# diskohedron4w_revc_autoroute.net
KiCad netlist of a schematic drawn in EAGLE
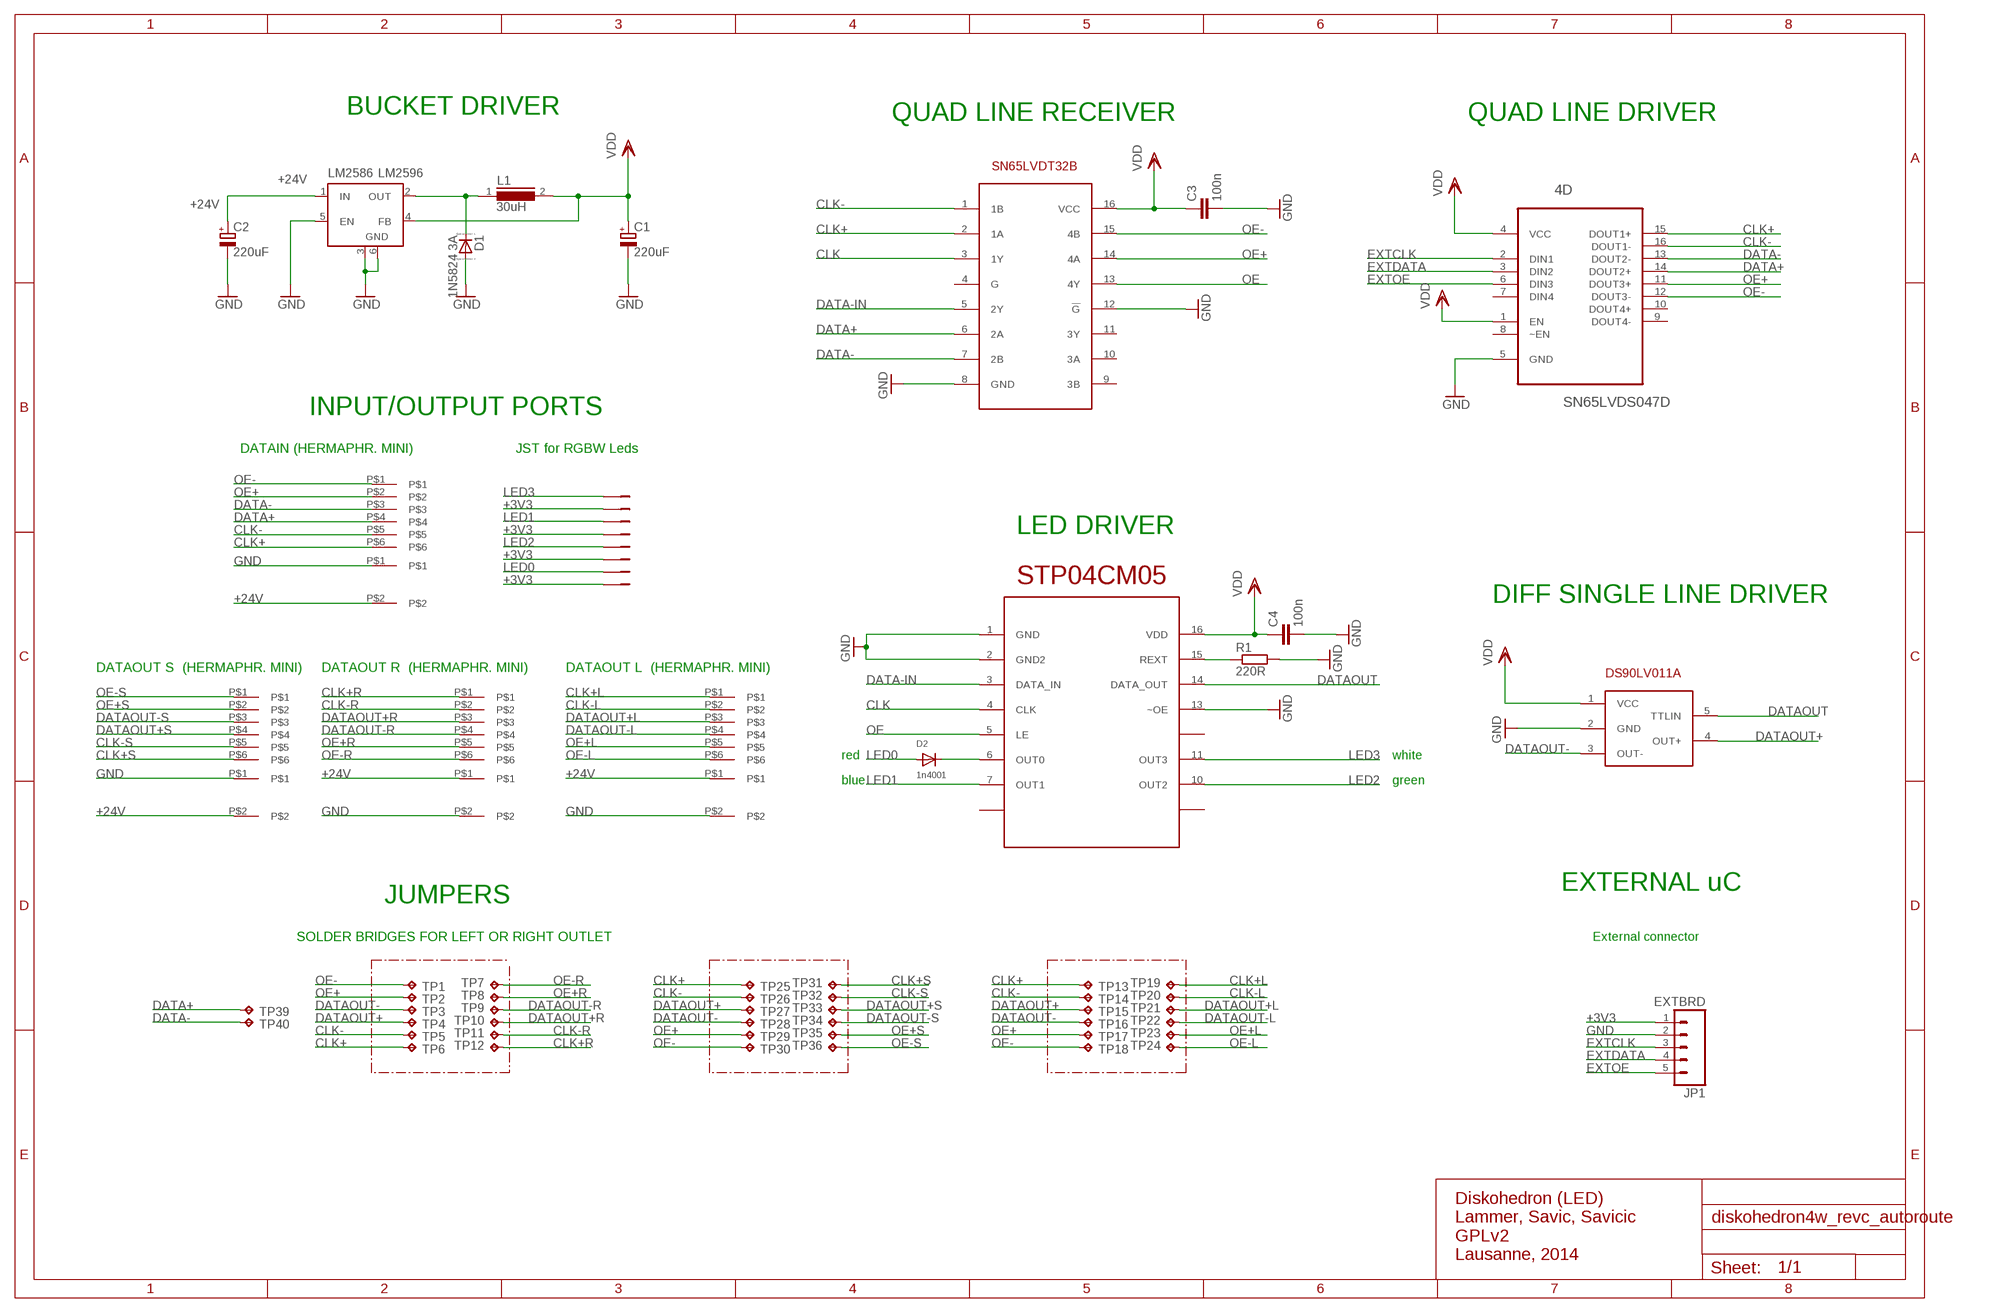
[diagram p0: schematic, sheet 1]

(export (version "E")
  (design (tool "Eeschema 10.0.6"))
  (components
    (comp (ref "1D")
      (value "DS90LV011A")
      (footprint "eagle-import:SOT23-5")
      (libsource (lib "eagle-import") (part "DS90LV011A"))
    )
    (comp (ref "4D")
      (value "SN65LVDS047D")
      (footprint "eagle-import:SOIC127P600X175-16N")
      (libsource (lib "eagle-import") (part "SN65LVDS047D"))
    )
    (comp (ref "4R")
      (value "SN65LVDST32")
      (footprint "eagle-import:SOIC16")
      (libsource (lib "eagle-import") (part "SN65LVDST32"))
    )
    (comp (ref "C1")
      (value "220uF")
      (footprint "eagle-import:175TMP-0810")
      (libsource (lib "eagle-import") (part "CPOL-EU175TMP-0810"))
    )
    (comp (ref "C2")
      (value "220uF")
      (footprint "eagle-import:175TMP-0810")
      (libsource (lib "eagle-import") (part "CPOL-EU175TMP-0810"))
    )
    (comp (ref "C3")
      (value "100n")
      (footprint "eagle-import:C0805")
      (libsource (lib "eagle-import") (part "C-EUC0805"))
    )
    (comp (ref "C4")
      (value "100n")
      (footprint "eagle-import:C0805")
      (libsource (lib "eagle-import") (part "C-EUC0805"))
    )
    (comp (ref "D1")
      (value "1N5824 3A")
      (footprint "eagle-import:DIODE_SMC")
      (libsource (lib "eagle-import") (part "DIODE_E-SMC"))
    )
    (comp (ref "D2")
      (value "1n4001")
      (footprint "eagle-import:SMADIODE")
      (libsource (lib "eagle-import") (part "DIODESMA"))
    )
    (comp (ref "IN1")
      (value "HERMAPHRODITMINI6PIN")
      (footprint "eagle-import:HERMAPHRODITMINI6PIN")
      (libsource (lib "eagle-import") (part "HERMAPHRODITMINI6PIN"))
    )
    (comp (ref "JP1")
      (value "EXTBRD")
      (footprint "eagle-import:1X05")
      (libsource (lib "eagle-import") (part "M05PTH"))
    )
    (comp (ref "JST")
      (value "8PIN-ZH")
      (footprint "eagle-import:B8B-ZH")
      (libsource (lib "eagle-import") (part "8PIN-ZH"))
    )
    (comp (ref "L1")
      (value "30uH")
      (footprint "eagle-import:DR127")
      (libsource (lib "eagle-import") (part "DR127"))
    )
    (comp (ref "LM2586")
      (value "LM2596")
      (footprint "eagle-import:TO263-5")
      (libsource (lib "eagle-import") (part "LM2596S"))
    )
    (comp (ref "OUT-L")
      (value "HERMAPHRODITMINI6PIN")
      (footprint "eagle-import:HERMAPHRODITMINI6PIN")
      (libsource (lib "eagle-import") (part "HERMAPHRODITMINI6PIN"))
    )
    (comp (ref "OUT-R")
      (value "HERMAPHRODITMINI6PIN")
      (footprint "eagle-import:HERMAPHRODITMINI6PIN")
      (libsource (lib "eagle-import") (part "HERMAPHRODITMINI6PIN"))
    )
    (comp (ref "OUT-R1")
      (value "HERMAPHRODITMINI6PIN")
      (footprint "eagle-import:HERMAPHRODITMINI6PIN")
      (libsource (lib "eagle-import") (part "HERMAPHRODITMINI6PIN"))
    )
    (comp (ref "R1")
      (value "220R")
      (footprint "eagle-import:M0805")
      (libsource (lib "eagle-import") (part "R-EU_M0805"))
    )
    (comp (ref "STP04")
      (value "STP04CM05")
      (footprint "eagle-import:TSSOP16")
      (libsource (lib "eagle-import") (part "STP04CM05"))
    )
    (comp (ref "TP1")
      (value "TPTP12SQ")
      (footprint "eagle-import:TP12SQ")
      (libsource (lib "eagle-import") (part "TPTP12SQ"))
    )
    (comp (ref "TP2")
      (value "TPTP12SQ")
      (footprint "eagle-import:TP12SQ")
      (libsource (lib "eagle-import") (part "TPTP12SQ"))
    )
    (comp (ref "TP3")
      (value "TPTP09SQ")
      (footprint "eagle-import:TP09SQ")
      (libsource (lib "eagle-import") (part "TPTP09SQ"))
    )
    (comp (ref "TP4")
      (value "TPTP09SQ")
      (footprint "eagle-import:TP09SQ")
      (libsource (lib "eagle-import") (part "TPTP09SQ"))
    )
    (comp (ref "TP5")
      (value "TPTP12SQ")
      (footprint "eagle-import:TP12SQ")
      (libsource (lib "eagle-import") (part "TPTP12SQ"))
    )
    (comp (ref "TP6")
      (value "TPTP12SQ")
      (footprint "eagle-import:TP12SQ")
      (libsource (lib "eagle-import") (part "TPTP12SQ"))
    )
    (comp (ref "TP7")
      (value "TPTP12SQ")
      (footprint "eagle-import:TP12SQ")
      (libsource (lib "eagle-import") (part "TPTP12SQ"))
    )
    (comp (ref "TP8")
      (value "TPTP12SQ")
      (footprint "eagle-import:TP12SQ")
      (libsource (lib "eagle-import") (part "TPTP12SQ"))
    )
    (comp (ref "TP9")
      (value "TPTP19SQ")
      (footprint "eagle-import:TP19SQ")
      (libsource (lib "eagle-import") (part "TPTP19SQ"))
    )
    (comp (ref "TP10")
      (value "TPTP19SQ")
      (footprint "eagle-import:TP19SQ")
      (libsource (lib "eagle-import") (part "TPTP19SQ"))
    )
    (comp (ref "TP11")
      (value "TPTP12SQ")
      (footprint "eagle-import:TP12SQ")
      (libsource (lib "eagle-import") (part "TPTP12SQ"))
    )
    (comp (ref "TP12")
      (value "TPTP12SQ")
      (footprint "eagle-import:TP12SQ")
      (libsource (lib "eagle-import") (part "TPTP12SQ"))
    )
    (comp (ref "TP13")
      (value "TPTP12SQ")
      (footprint "eagle-import:TP12SQ")
      (libsource (lib "eagle-import") (part "TPTP12SQ"))
    )
    (comp (ref "TP14")
      (value "TPTP12SQ")
      (footprint "eagle-import:TP12SQ")
      (libsource (lib "eagle-import") (part "TPTP12SQ"))
    )
    (comp (ref "TP15")
      (value "TPTP12SQ")
      (footprint "eagle-import:TP12SQ")
      (libsource (lib "eagle-import") (part "TPTP12SQ"))
    )
    (comp (ref "TP16")
      (value "TPTP12SQ")
      (footprint "eagle-import:TP12SQ")
      (libsource (lib "eagle-import") (part "TPTP12SQ"))
    )
    (comp (ref "TP17")
      (value "TPTP12SQ")
      (footprint "eagle-import:TP12SQ")
      (libsource (lib "eagle-import") (part "TPTP12SQ"))
    )
    (comp (ref "TP18")
      (value "TPTP12SQ")
      (footprint "eagle-import:TP12SQ")
      (libsource (lib "eagle-import") (part "TPTP12SQ"))
    )
    (comp (ref "TP19")
      (value "TPTP12SQ")
      (footprint "eagle-import:TP12SQ")
      (libsource (lib "eagle-import") (part "TPTP12SQ"))
    )
    (comp (ref "TP20")
      (value "TPTP12SQ")
      (footprint "eagle-import:TP12SQ")
      (libsource (lib "eagle-import") (part "TPTP12SQ"))
    )
    (comp (ref "TP21")
      (value "TPTP12SQ")
      (footprint "eagle-import:TP12SQ")
      (libsource (lib "eagle-import") (part "TPTP12SQ"))
    )
    (comp (ref "TP22")
      (value "TPTP12SQ")
      (footprint "eagle-import:TP12SQ")
      (libsource (lib "eagle-import") (part "TPTP12SQ"))
    )
    (comp (ref "TP23")
      (value "TPTP12SQ")
      (footprint "eagle-import:TP12SQ")
      (libsource (lib "eagle-import") (part "TPTP12SQ"))
    )
    (comp (ref "TP24")
      (value "TPTP12SQ")
      (footprint "eagle-import:TP12SQ")
      (libsource (lib "eagle-import") (part "TPTP12SQ"))
    )
    (comp (ref "TP25")
      (value "TPTP12SQ")
      (footprint "eagle-import:TP12SQ")
      (libsource (lib "eagle-import") (part "TPTP12SQ"))
    )
    (comp (ref "TP26")
      (value "TPTP12SQ")
      (footprint "eagle-import:TP12SQ")
      (libsource (lib "eagle-import") (part "TPTP12SQ"))
    )
    (comp (ref "TP27")
      (value "TPTP12SQ")
      (footprint "eagle-import:TP12SQ")
      (libsource (lib "eagle-import") (part "TPTP12SQ"))
    )
    (comp (ref "TP28")
      (value "TPTP12SQ")
      (footprint "eagle-import:TP12SQ")
      (libsource (lib "eagle-import") (part "TPTP12SQ"))
    )
    (comp (ref "TP29")
      (value "TPTP12SQ")
      (footprint "eagle-import:TP12SQ")
      (libsource (lib "eagle-import") (part "TPTP12SQ"))
    )
    (comp (ref "TP30")
      (value "TPTP12SQ")
      (footprint "eagle-import:TP12SQ")
      (libsource (lib "eagle-import") (part "TPTP12SQ"))
    )
    (comp (ref "TP31")
      (value "TPTP12SQ")
      (footprint "eagle-import:TP12SQ")
      (libsource (lib "eagle-import") (part "TPTP12SQ"))
    )
    (comp (ref "TP32")
      (value "TPTP12SQ")
      (footprint "eagle-import:TP12SQ")
      (libsource (lib "eagle-import") (part "TPTP12SQ"))
    )
    (comp (ref "TP33")
      (value "TPTP12SQ")
      (footprint "eagle-import:TP12SQ")
      (libsource (lib "eagle-import") (part "TPTP12SQ"))
    )
    (comp (ref "TP34")
      (value "TPTP12SQ")
      (footprint "eagle-import:TP12SQ")
      (libsource (lib "eagle-import") (part "TPTP12SQ"))
    )
    (comp (ref "TP35")
      (value "TPTP12SQ")
      (footprint "eagle-import:TP12SQ")
      (libsource (lib "eagle-import") (part "TPTP12SQ"))
    )
    (comp (ref "TP36")
      (value "TPTP12SQ")
      (footprint "eagle-import:TP12SQ")
      (libsource (lib "eagle-import") (part "TPTP12SQ"))
    )
    (comp (ref "TP39")
      (value "TPTP09SQ")
      (footprint "eagle-import:TP09SQ")
      (libsource (lib "eagle-import") (part "TPTP09SQ"))
    )
    (comp (ref "TP40")
      (value "TPTP09SQ")
      (footprint "eagle-import:TP09SQ")
      (libsource (lib "eagle-import") (part "TPTP09SQ"))
    )
    (comp (ref "U$1")
      (value "HERMAPHRODIT2PIN")
      (footprint "eagle-import:HERMAPHRODIT2PIN")
      (libsource (lib "eagle-import") (part "HERMAPHRODIT2PIN"))
    )
    (comp (ref "U$6")
      (value "HERMAPHRODIT2PIN")
      (footprint "eagle-import:HERMAPHRODIT2PIN")
      (libsource (lib "eagle-import") (part "HERMAPHRODIT2PIN"))
    )
    (comp (ref "U$7")
      (value "HERMAPHRODIT2PIN")
      (footprint "eagle-import:HERMAPHRODIT2PIN")
      (libsource (lib "eagle-import") (part "HERMAPHRODIT2PIN"))
    )
    (comp (ref "U$12")
      (value "HERMAPHRODIT2PIN")
      (footprint "eagle-import:HERMAPHRODIT2PIN")
      (libsource (lib "eagle-import") (part "HERMAPHRODIT2PIN"))
    )
  )
  (nets
    (net (code "1") (name "/+24V") (class "Default")
      (node (ref "C2") (pin "+") (pinfunction "+_+") (pintype "passive"))
      (node (ref "LM2586") (pin "1") (pinfunction "IN_1") (pintype "input"))
      (node (ref "U$1") (pin "P$2") (pinfunction "P$2_P$2") (pintype "bidirectional"))
      (node (ref "U$12") (pin "P$1") (pinfunction "P$1_P$1") (pintype "bidirectional"))
      (node (ref "U$6") (pin "P$1") (pinfunction "P$1_P$1") (pintype "bidirectional"))
      (node (ref "U$7") (pin "P$2") (pinfunction "P$2_P$2") (pintype "bidirectional"))
    )
    (net (code "2") (name "/CLK") (class "Default")
      (node (ref "4R") (pin "3") (pinfunction "1Y_3") (pintype "bidirectional"))
      (node (ref "STP04") (pin "4") (pinfunction "CLK_4") (pintype "bidirectional"))
    )
    (net (code "3") (name "/CLK+") (class "Default")
      (node (ref "4D") (pin "15") (pinfunction "DOUT1+_15") (pintype "output"))
      (node (ref "4R") (pin "2") (pinfunction "1A_2") (pintype "bidirectional"))
      (node (ref "IN1") (pin "P$6") (pinfunction "P$6_P$6") (pintype "bidirectional"))
      (node (ref "TP13") (pin "TP") (pinfunction "TP_TP") (pintype "input"))
      (node (ref "TP25") (pin "TP") (pinfunction "TP_TP") (pintype "input"))
      (node (ref "TP6") (pin "TP") (pinfunction "TP_TP") (pintype "input"))
    )
    (net (code "4") (name "/CLK+L") (class "Default")
      (node (ref "OUT-L") (pin "P$1") (pinfunction "P$1_P$1") (pintype "bidirectional"))
      (node (ref "TP19") (pin "TP") (pinfunction "TP_TP") (pintype "input"))
    )
    (net (code "5") (name "/CLK+R") (class "Default")
      (node (ref "OUT-R") (pin "P$1") (pinfunction "P$1_P$1") (pintype "bidirectional"))
      (node (ref "TP12") (pin "TP") (pinfunction "TP_TP") (pintype "input"))
    )
    (net (code "6") (name "/CLK+S") (class "Default")
      (node (ref "OUT-R1") (pin "P$6") (pinfunction "P$6_P$6") (pintype "bidirectional"))
      (node (ref "TP31") (pin "TP") (pinfunction "TP_TP") (pintype "input"))
    )
    (net (code "7") (name "/CLK-") (class "Default")
      (node (ref "4D") (pin "16") (pinfunction "DOUT1-_16") (pintype "output"))
      (node (ref "4R") (pin "1") (pinfunction "1B_1") (pintype "bidirectional"))
      (node (ref "IN1") (pin "P$5") (pinfunction "P$5_P$5") (pintype "bidirectional"))
      (node (ref "TP14") (pin "TP") (pinfunction "TP_TP") (pintype "input"))
      (node (ref "TP26") (pin "TP") (pinfunction "TP_TP") (pintype "input"))
      (node (ref "TP5") (pin "TP") (pinfunction "TP_TP") (pintype "input"))
    )
    (net (code "8") (name "/CLK-L") (class "Default")
      (node (ref "OUT-L") (pin "P$2") (pinfunction "P$2_P$2") (pintype "bidirectional"))
      (node (ref "TP20") (pin "TP") (pinfunction "TP_TP") (pintype "input"))
    )
    (net (code "9") (name "/CLK-R") (class "Default")
      (node (ref "OUT-R") (pin "P$2") (pinfunction "P$2_P$2") (pintype "bidirectional"))
      (node (ref "TP11") (pin "TP") (pinfunction "TP_TP") (pintype "input"))
    )
    (net (code "10") (name "/CLK-S") (class "Default")
      (node (ref "OUT-R1") (pin "P$5") (pinfunction "P$5_P$5") (pintype "bidirectional"))
      (node (ref "TP32") (pin "TP") (pinfunction "TP_TP") (pintype "input"))
    )
    (net (code "11") (name "/DATA+") (class "Default")
      (node (ref "4D") (pin "14") (pinfunction "DOUT2+_14") (pintype "output"))
      (node (ref "4R") (pin "6") (pinfunction "2A_6") (pintype "bidirectional"))
      (node (ref "IN1") (pin "P$4") (pinfunction "P$4_P$4") (pintype "bidirectional"))
      (node (ref "TP39") (pin "TP") (pinfunction "TP_TP") (pintype "input"))
    )
    (net (code "12") (name "/DATA-") (class "Default")
      (node (ref "4D") (pin "13") (pinfunction "DOUT2-_13") (pintype "output"))
      (node (ref "4R") (pin "7") (pinfunction "2B_7") (pintype "bidirectional"))
      (node (ref "IN1") (pin "P$3") (pinfunction "P$3_P$3") (pintype "bidirectional"))
      (node (ref "TP40") (pin "TP") (pinfunction "TP_TP") (pintype "input"))
    )
    (net (code "13") (name "/DATA-IN") (class "Default")
      (node (ref "4R") (pin "5") (pinfunction "2Y_5") (pintype "bidirectional"))
      (node (ref "STP04") (pin "3") (pinfunction "DATA_IN_3") (pintype "bidirectional"))
    )
    (net (code "14") (name "/DATAOUT") (class "Default")
      (node (ref "1D") (pin "5") (pinfunction "TTLIN_5") (pintype "bidirectional"))
      (node (ref "STP04") (pin "14") (pinfunction "DATA_OUT_14") (pintype "bidirectional"))
    )
    (net (code "15") (name "/DATAOUT+") (class "Default")
      (node (ref "1D") (pin "4") (pinfunction "OUT+_4") (pintype "bidirectional"))
      (node (ref "TP15") (pin "TP") (pinfunction "TP_TP") (pintype "input"))
      (node (ref "TP27") (pin "TP") (pinfunction "TP_TP") (pintype "input"))
      (node (ref "TP4") (pin "TP") (pinfunction "TP_TP") (pintype "input"))
    )
    (net (code "16") (name "/DATAOUT+L") (class "Default")
      (node (ref "OUT-L") (pin "P$3") (pinfunction "P$3_P$3") (pintype "bidirectional"))
      (node (ref "TP21") (pin "TP") (pinfunction "TP_TP") (pintype "input"))
    )
    (net (code "17") (name "/DATAOUT+R") (class "Default")
      (node (ref "OUT-R") (pin "P$3") (pinfunction "P$3_P$3") (pintype "bidirectional"))
      (node (ref "TP10") (pin "TP") (pinfunction "TP_TP") (pintype "input"))
    )
    (net (code "18") (name "/DATAOUT+S") (class "Default")
      (node (ref "OUT-R1") (pin "P$4") (pinfunction "P$4_P$4") (pintype "bidirectional"))
      (node (ref "TP33") (pin "TP") (pinfunction "TP_TP") (pintype "input"))
    )
    (net (code "19") (name "/DATAOUT-") (class "Default")
      (node (ref "1D") (pin "3") (pinfunction "OUT-_3") (pintype "bidirectional"))
      (node (ref "TP16") (pin "TP") (pinfunction "TP_TP") (pintype "input"))
      (node (ref "TP28") (pin "TP") (pinfunction "TP_TP") (pintype "input"))
      (node (ref "TP3") (pin "TP") (pinfunction "TP_TP") (pintype "input"))
    )
    (net (code "20") (name "/DATAOUT-L") (class "Default")
      (node (ref "OUT-L") (pin "P$4") (pinfunction "P$4_P$4") (pintype "bidirectional"))
      (node (ref "TP22") (pin "TP") (pinfunction "TP_TP") (pintype "input"))
    )
    (net (code "21") (name "/DATAOUT-R") (class "Default")
      (node (ref "OUT-R") (pin "P$4") (pinfunction "P$4_P$4") (pintype "bidirectional"))
      (node (ref "TP9") (pin "TP") (pinfunction "TP_TP") (pintype "input"))
    )
    (net (code "22") (name "/DATAOUT-S") (class "Default")
      (node (ref "OUT-R1") (pin "P$3") (pinfunction "P$3_P$3") (pintype "bidirectional"))
      (node (ref "TP34") (pin "TP") (pinfunction "TP_TP") (pintype "input"))
    )
    (net (code "23") (name "/EXTCLK") (class "Default")
      (node (ref "4D") (pin "2") (pinfunction "DIN1_2") (pintype "input"))
      (node (ref "JP1") (pin "3") (pinfunction "3_3") (pintype "passive"))
    )
    (net (code "24") (name "/EXTDATA") (class "Default")
      (node (ref "4D") (pin "3") (pinfunction "DIN2_3") (pintype "input"))
      (node (ref "JP1") (pin "4") (pinfunction "4_4") (pintype "passive"))
    )
    (net (code "25") (name "/EXTOE") (class "Default")
      (node (ref "4D") (pin "6") (pinfunction "DIN3_6") (pintype "input"))
      (node (ref "JP1") (pin "5") (pinfunction "5_5") (pintype "passive"))
    )
    (net (code "26") (name "/LED0") (class "Default")
      (node (ref "D2") (pin "A") (pinfunction "A_A") (pintype "passive"))
      (node (ref "JST") (pin "7") (pinfunction "1_7") (pintype "passive"))
    )
    (net (code "27") (name "/LED1") (class "Default")
      (node (ref "JST") (pin "3") (pinfunction "1_3") (pintype "passive"))
      (node (ref "STP04") (pin "7") (pinfunction "OUT1_7") (pintype "bidirectional"))
    )
    (net (code "28") (name "/LED2") (class "Default")
      (node (ref "JST") (pin "5") (pinfunction "1_5") (pintype "passive"))
      (node (ref "STP04") (pin "10") (pinfunction "OUT2_10") (pintype "bidirectional"))
    )
    (net (code "29") (name "/LED3") (class "Default")
      (node (ref "JST") (pin "1") (pinfunction "1_1") (pintype "passive"))
      (node (ref "STP04") (pin "11") (pinfunction "OUT3_11") (pintype "bidirectional"))
    )
    (net (code "30") (name "/OE") (class "Default")
      (node (ref "4R") (pin "13") (pinfunction "4Y_13") (pintype "bidirectional"))
      (node (ref "STP04") (pin "5") (pinfunction "LE_5") (pintype "bidirectional"))
    )
    (net (code "31") (name "/OE+") (class "Default")
      (node (ref "4D") (pin "11") (pinfunction "DOUT3+_11") (pintype "output"))
      (node (ref "4R") (pin "14") (pinfunction "4A_14") (pintype "bidirectional"))
      (node (ref "IN1") (pin "P$2") (pinfunction "P$2_P$2") (pintype "bidirectional"))
      (node (ref "TP17") (pin "TP") (pinfunction "TP_TP") (pintype "input"))
      (node (ref "TP2") (pin "TP") (pinfunction "TP_TP") (pintype "input"))
      (node (ref "TP29") (pin "TP") (pinfunction "TP_TP") (pintype "input"))
    )
    (net (code "32") (name "/OE+L") (class "Default")
      (node (ref "OUT-L") (pin "P$5") (pinfunction "P$5_P$5") (pintype "bidirectional"))
      (node (ref "TP23") (pin "TP") (pinfunction "TP_TP") (pintype "input"))
    )
    (net (code "33") (name "/OE+R") (class "Default")
      (node (ref "OUT-R") (pin "P$5") (pinfunction "P$5_P$5") (pintype "bidirectional"))
      (node (ref "TP8") (pin "TP") (pinfunction "TP_TP") (pintype "input"))
    )
    (net (code "34") (name "/OE+S") (class "Default")
      (node (ref "OUT-R1") (pin "P$2") (pinfunction "P$2_P$2") (pintype "bidirectional"))
      (node (ref "TP35") (pin "TP") (pinfunction "TP_TP") (pintype "input"))
    )
    (net (code "35") (name "/OE-") (class "Default")
      (node (ref "4D") (pin "12") (pinfunction "DOUT3-_12") (pintype "output"))
      (node (ref "4R") (pin "15") (pinfunction "4B_15") (pintype "bidirectional"))
      (node (ref "IN1") (pin "P$1") (pinfunction "P$1_P$1") (pintype "bidirectional"))
      (node (ref "TP1") (pin "TP") (pinfunction "TP_TP") (pintype "input"))
      (node (ref "TP18") (pin "TP") (pinfunction "TP_TP") (pintype "input"))
      (node (ref "TP30") (pin "TP") (pinfunction "TP_TP") (pintype "input"))
    )
    (net (code "36") (name "/OE-L") (class "Default")
      (node (ref "OUT-L") (pin "P$6") (pinfunction "P$6_P$6") (pintype "bidirectional"))
      (node (ref "TP24") (pin "TP") (pinfunction "TP_TP") (pintype "input"))
    )
    (net (code "37") (name "/OE-R") (class "Default")
      (node (ref "OUT-R") (pin "P$6") (pinfunction "P$6_P$6") (pintype "bidirectional"))
      (node (ref "TP7") (pin "TP") (pinfunction "TP_TP") (pintype "input"))
    )
    (net (code "38") (name "/OE-S") (class "Default")
      (node (ref "OUT-R1") (pin "P$1") (pinfunction "P$1_P$1") (pintype "bidirectional"))
      (node (ref "TP36") (pin "TP") (pinfunction "TP_TP") (pintype "input"))
    )
    (net (code "39") (name "GND") (class "Default")
      (node (ref "1D") (pin "2") (pinfunction "GND_2") (pintype "bidirectional"))
      (node (ref "4D") (pin "5") (pinfunction "GND_5") (pintype "passive"))
      (node (ref "4R") (pin "12") (pinfunction "~{G}_12") (pintype "bidirectional"))
      (node (ref "4R") (pin "8") (pinfunction "GND_8") (pintype "bidirectional"))
      (node (ref "C1") (pin "-") (pinfunction "-_-") (pintype "passive"))
      (node (ref "C2") (pin "-") (pinfunction "-_-") (pintype "passive"))
      (node (ref "C3") (pin "2") (pinfunction "2_2") (pintype "passive"))
      (node (ref "C4") (pin "2") (pinfunction "2_2") (pintype "passive"))
      (node (ref "D1") (pin "A") (pinfunction "C_A") (pintype "passive"))
      (node (ref "JP1") (pin "2") (pinfunction "2_2") (pintype "passive"))
      (node (ref "LM2586") (pin "3") (pinfunction "GND_3") (pintype "power_in"))
      (node (ref "LM2586") (pin "5") (pinfunction "EN_5") (pintype "input"))
      (node (ref "LM2586") (pin "6") (pinfunction "GND_6") (pintype "power_in"))
      (node (ref "R1") (pin "2") (pinfunction "2_2") (pintype "passive"))
      (node (ref "STP04") (pin "1") (pinfunction "GND_1") (pintype "bidirectional"))
      (node (ref "STP04") (pin "13") (pinfunction "~{OE}_13") (pintype "bidirectional"))
      (node (ref "STP04") (pin "2") (pinfunction "GND2_2") (pintype "bidirectional"))
      (node (ref "U$1") (pin "P$1") (pinfunction "P$1_P$1") (pintype "bidirectional"))
      (node (ref "U$12") (pin "P$2") (pinfunction "P$2_P$2") (pintype "bidirectional"))
      (node (ref "U$6") (pin "P$2") (pinfunction "P$2_P$2") (pintype "bidirectional"))
      (node (ref "U$7") (pin "P$1") (pinfunction "P$1_P$1") (pintype "bidirectional"))
    )
    (net (code "40") (name "Net-(D1-A)") (class "Default")
      (node (ref "D1") (pin "C") (pinfunction "A_C") (pintype "passive"))
      (node (ref "L1") (pin "1") (pinfunction "1_1") (pintype "passive"))
      (node (ref "LM2586") (pin "2") (pinfunction "OUT_2") (pintype "output"))
    )
    (net (code "41") (name "Net-(STP04-OUT0)") (class "Default")
      (node (ref "D2") (pin "C") (pinfunction "C_C") (pintype "passive"))
      (node (ref "STP04") (pin "6") (pinfunction "OUT0_6") (pintype "bidirectional"))
    )
    (net (code "42") (name "Net-(STP04-REXT)") (class "Default")
      (node (ref "R1") (pin "1") (pinfunction "1_1") (pintype "passive"))
      (node (ref "STP04") (pin "15") (pinfunction "REXT_15") (pintype "bidirectional"))
    )
    (net (code "43") (name "VDD") (class "Default")
      (node (ref "1D") (pin "1") (pinfunction "VCC_1") (pintype "bidirectional"))
      (node (ref "4D") (pin "1") (pinfunction "EN_1") (pintype "input"))
      (node (ref "4D") (pin "4") (pinfunction "VCC_4") (pintype "power_in"))
      (node (ref "4R") (pin "16") (pinfunction "VCC_16") (pintype "bidirectional"))
      (node (ref "C1") (pin "+") (pinfunction "+_+") (pintype "passive"))
      (node (ref "C3") (pin "1") (pinfunction "1_1") (pintype "passive"))
      (node (ref "C4") (pin "1") (pinfunction "1_1") (pintype "passive"))
      (node (ref "JP1") (pin "1") (pinfunction "1_1") (pintype "passive"))
      (node (ref "JST") (pin "2") (pinfunction "1_2") (pintype "passive"))
      (node (ref "JST") (pin "4") (pinfunction "1_4") (pintype "passive"))
      (node (ref "JST") (pin "6") (pinfunction "1_6") (pintype "passive"))
      (node (ref "JST") (pin "8") (pinfunction "1_8") (pintype "passive"))
      (node (ref "L1") (pin "2") (pinfunction "2_2") (pintype "passive"))
      (node (ref "LM2586") (pin "4") (pinfunction "FB_4") (pintype "input"))
      (node (ref "STP04") (pin "16") (pinfunction "VDD_16") (pintype "bidirectional"))
    )
    (net (code "44") (name "unconnected-(4D-DIN4-Pad7)") (class "Default")
      (node (ref "4D") (pin "7") (pinfunction "DIN4_7") (pintype "input"))
    )
    (net (code "45") (name "unconnected-(4D-DOUT4+-Pad10)") (class "Default")
      (node (ref "4D") (pin "10") (pinfunction "DOUT4+_10") (pintype "output"))
    )
    (net (code "46") (name "unconnected-(4D-DOUT4--Pad9)") (class "Default")
      (node (ref "4D") (pin "9") (pinfunction "DOUT4-_9") (pintype "output"))
    )
    (net (code "47") (name "unconnected-(4D-~{EN}-Pad8)") (class "Default")
      (node (ref "4D") (pin "8") (pinfunction "~{EN}_8") (pintype "input"))
    )
    (net (code "48") (name "unconnected-(4R-3A-Pad10)") (class "Default")
      (node (ref "4R") (pin "10") (pinfunction "3A_10") (pintype "bidirectional"))
    )
    (net (code "49") (name "unconnected-(4R-3B-Pad9)") (class "Default")
      (node (ref "4R") (pin "9") (pinfunction "3B_9") (pintype "bidirectional"))
    )
    (net (code "50") (name "unconnected-(4R-3Y-Pad11)") (class "Default")
      (node (ref "4R") (pin "11") (pinfunction "3Y_11") (pintype "bidirectional"))
    )
    (net (code "51") (name "unconnected-(4R-G-Pad4)") (class "Default")
      (node (ref "4R") (pin "4") (pinfunction "G_4") (pintype "bidirectional"))
    )
    (net (code "52") (name "unconnected-(STP04-N.C1-Pad8)") (class "Default")
      (node (ref "STP04") (pin "8") (pinfunction "N.C1_8") (pintype "bidirectional"))
    )
    (net (code "53") (name "unconnected-(STP04-NC-Pad9)") (class "Default")
      (node (ref "STP04") (pin "9") (pinfunction "NC_9") (pintype "bidirectional"))
    )
    (net (code "54") (name "unconnected-(STP04-NC3-Pad12)") (class "Default")
      (node (ref "STP04") (pin "12") (pinfunction "NC3_12") (pintype "bidirectional"))
    )
  )
)
